# FlashAdapter.net
KiCad netlist of a schematic drawn in EAGLE
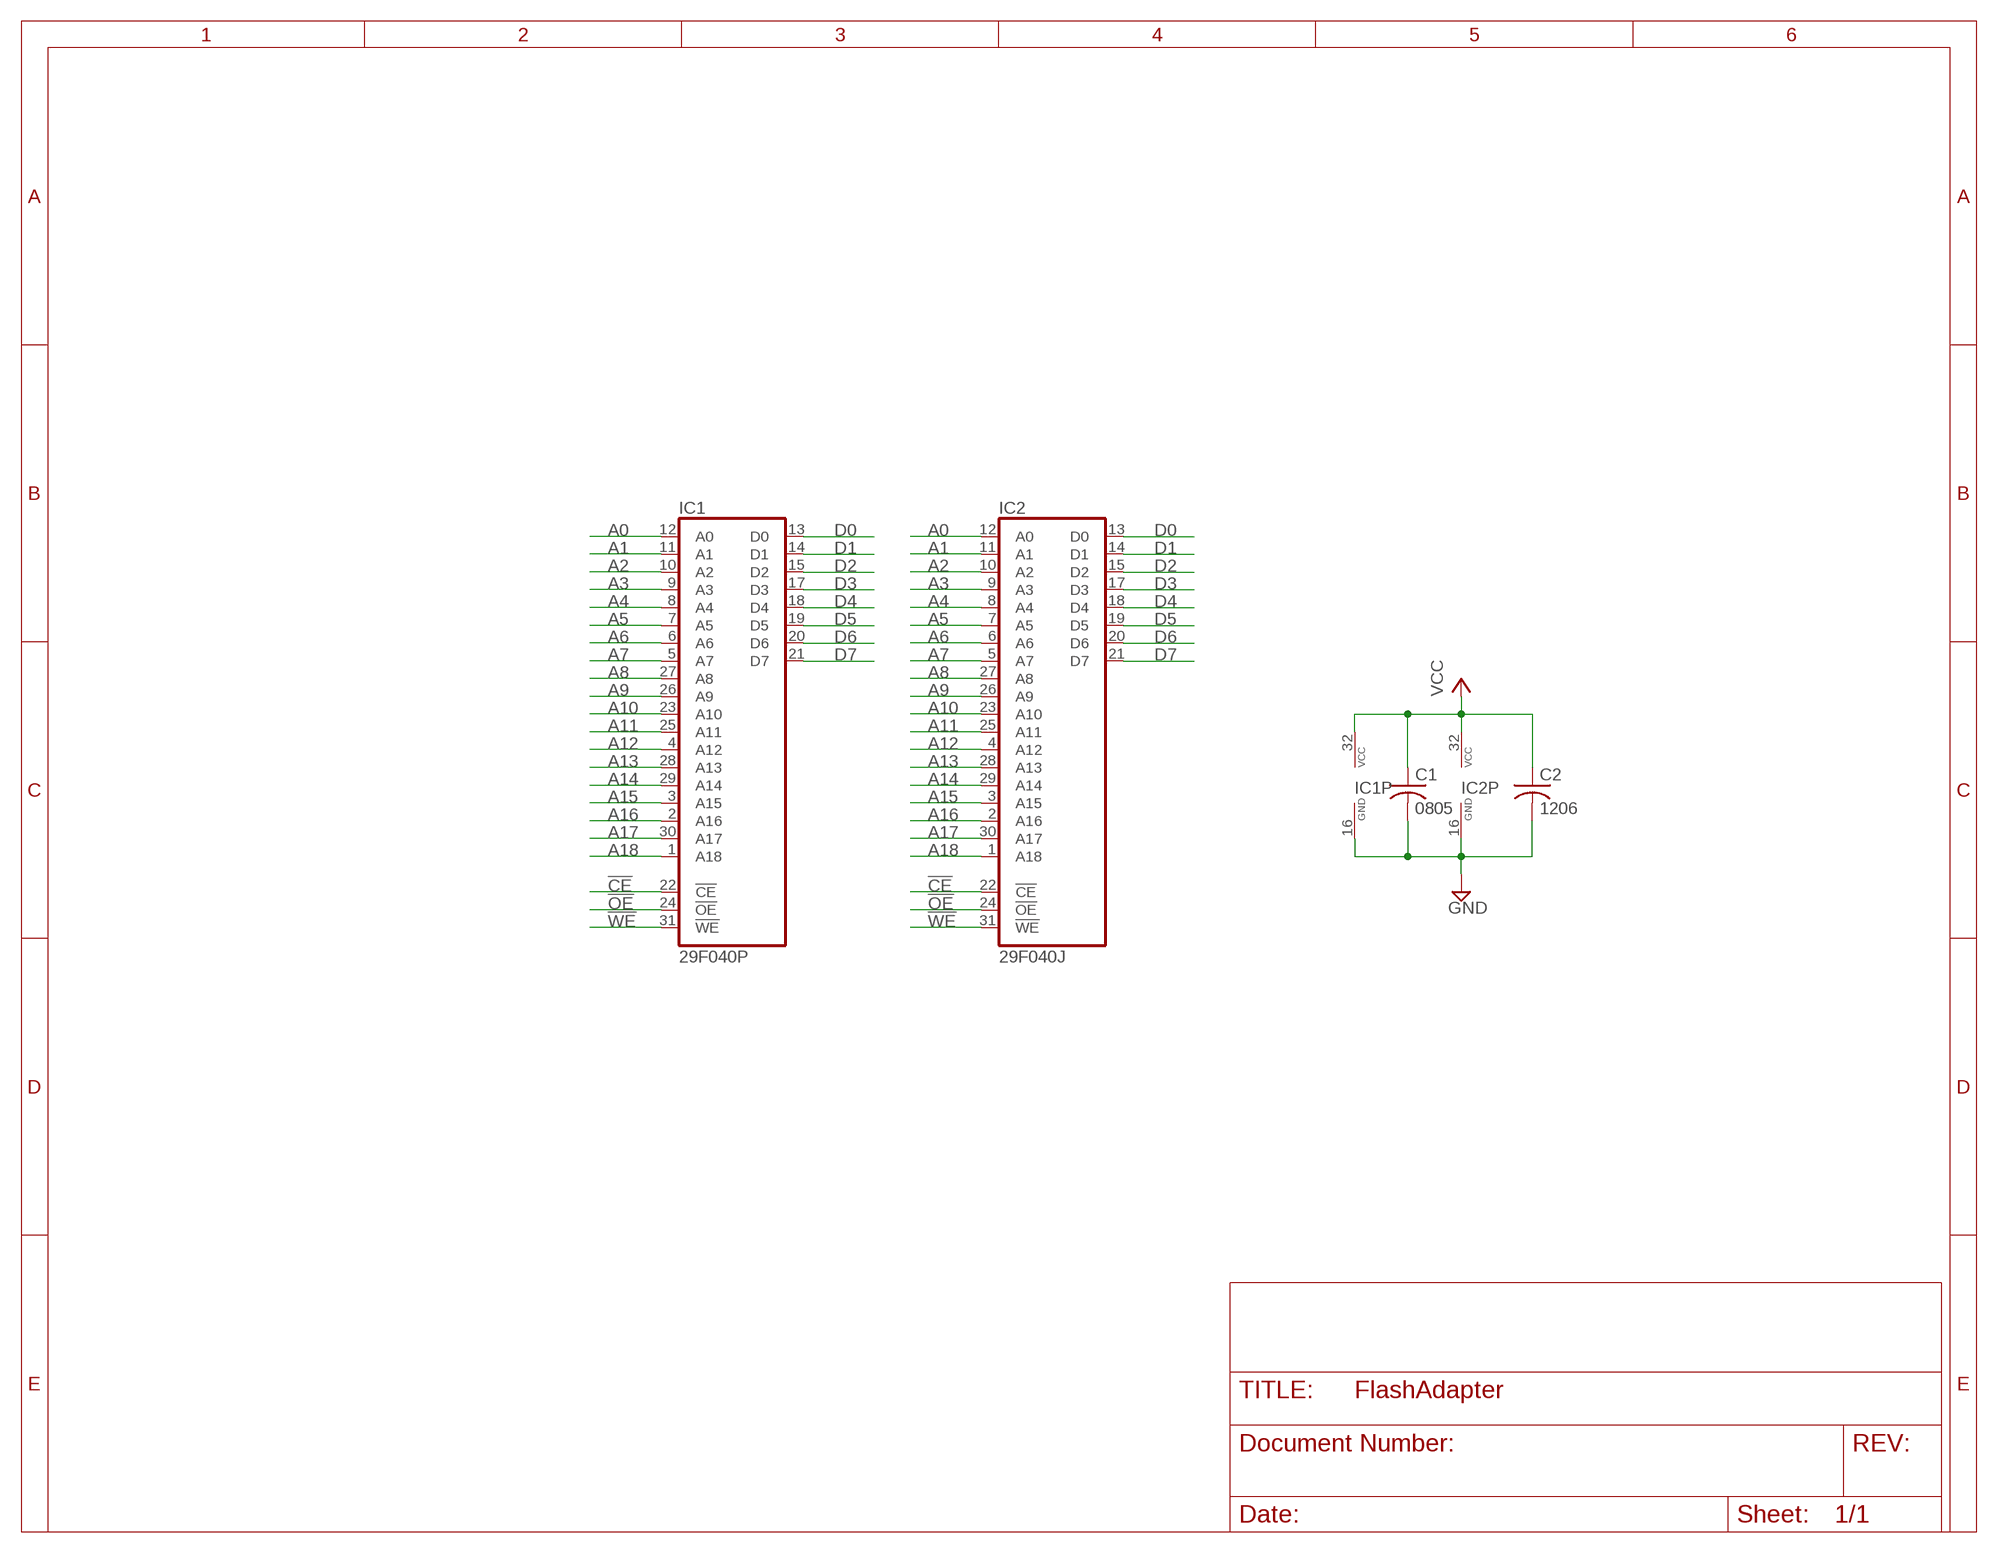
[diagram p0: schematic, sheet 1]

(export (version "E")
  (design (tool "Eeschema 10.0.6"))
  (components
    (comp (ref "C1")
      (value "0805")
      (footprint "eagle-import:C0805")
      (libsource (lib "eagle-import") (part "C-USC0805"))
    )
    (comp (ref "C2")
      (value "1206")
      (footprint "eagle-import:C1206")
      (libsource (lib "eagle-import") (part "C-USC1206"))
    )
    (comp (ref "IC1")
      (value "29F040P")
      (footprint "eagle-import:DIL32-3")
      (libsource (lib "eagle-import") (part "29F040P"))
    )
    (comp (ref "IC2")
      (value "29F040J")
      (footprint "eagle-import:S32")
      (libsource (lib "eagle-import") (part "29F040J"))
    )
  )
  (nets
    (net (code "1") (name "/A0") (class "Default")
      (node (ref "IC1") (pin "12") (pinfunction "A0_12") (pintype "input"))
      (node (ref "IC2") (pin "12") (pinfunction "A0_12") (pintype "input"))
    )
    (net (code "2") (name "/A1") (class "Default")
      (node (ref "IC1") (pin "11") (pinfunction "A1_11") (pintype "input"))
      (node (ref "IC2") (pin "11") (pinfunction "A1_11") (pintype "input"))
    )
    (net (code "3") (name "/A2") (class "Default")
      (node (ref "IC1") (pin "10") (pinfunction "A2_10") (pintype "input"))
      (node (ref "IC2") (pin "10") (pinfunction "A2_10") (pintype "input"))
    )
    (net (code "4") (name "/A3") (class "Default")
      (node (ref "IC1") (pin "9") (pinfunction "A3_9") (pintype "input"))
      (node (ref "IC2") (pin "9") (pinfunction "A3_9") (pintype "input"))
    )
    (net (code "5") (name "/A4") (class "Default")
      (node (ref "IC1") (pin "8") (pinfunction "A4_8") (pintype "input"))
      (node (ref "IC2") (pin "8") (pinfunction "A4_8") (pintype "input"))
    )
    (net (code "6") (name "/A5") (class "Default")
      (node (ref "IC1") (pin "7") (pinfunction "A5_7") (pintype "input"))
      (node (ref "IC2") (pin "7") (pinfunction "A5_7") (pintype "input"))
    )
    (net (code "7") (name "/A6") (class "Default")
      (node (ref "IC1") (pin "6") (pinfunction "A6_6") (pintype "input"))
      (node (ref "IC2") (pin "6") (pinfunction "A6_6") (pintype "input"))
    )
    (net (code "8") (name "/A7") (class "Default")
      (node (ref "IC1") (pin "5") (pinfunction "A7_5") (pintype "input"))
      (node (ref "IC2") (pin "5") (pinfunction "A7_5") (pintype "input"))
    )
    (net (code "9") (name "/A8") (class "Default")
      (node (ref "IC1") (pin "27") (pinfunction "A8_27") (pintype "input"))
      (node (ref "IC2") (pin "27") (pinfunction "A8_27") (pintype "input"))
    )
    (net (code "10") (name "/A9") (class "Default")
      (node (ref "IC1") (pin "26") (pinfunction "A9_26") (pintype "input"))
      (node (ref "IC2") (pin "26") (pinfunction "A9_26") (pintype "input"))
    )
    (net (code "11") (name "/A10") (class "Default")
      (node (ref "IC1") (pin "23") (pinfunction "A10_23") (pintype "input"))
      (node (ref "IC2") (pin "23") (pinfunction "A10_23") (pintype "input"))
    )
    (net (code "12") (name "/A11") (class "Default")
      (node (ref "IC1") (pin "25") (pinfunction "A11_25") (pintype "input"))
      (node (ref "IC2") (pin "25") (pinfunction "A11_25") (pintype "input"))
    )
    (net (code "13") (name "/A12") (class "Default")
      (node (ref "IC1") (pin "4") (pinfunction "A12_4") (pintype "input"))
      (node (ref "IC2") (pin "4") (pinfunction "A12_4") (pintype "input"))
    )
    (net (code "14") (name "/A13") (class "Default")
      (node (ref "IC1") (pin "28") (pinfunction "A13_28") (pintype "input"))
      (node (ref "IC2") (pin "28") (pinfunction "A13_28") (pintype "input"))
    )
    (net (code "15") (name "/A14") (class "Default")
      (node (ref "IC1") (pin "29") (pinfunction "A14_29") (pintype "input"))
      (node (ref "IC2") (pin "29") (pinfunction "A14_29") (pintype "input"))
    )
    (net (code "16") (name "/A15") (class "Default")
      (node (ref "IC1") (pin "3") (pinfunction "A15_3") (pintype "input"))
      (node (ref "IC2") (pin "3") (pinfunction "A15_3") (pintype "input"))
    )
    (net (code "17") (name "/A16") (class "Default")
      (node (ref "IC1") (pin "2") (pinfunction "A16_2") (pintype "input"))
      (node (ref "IC2") (pin "2") (pinfunction "A16_2") (pintype "input"))
    )
    (net (code "18") (name "/A17") (class "Default")
      (node (ref "IC1") (pin "30") (pinfunction "A17_30") (pintype "input"))
      (node (ref "IC2") (pin "30") (pinfunction "A17_30") (pintype "input"))
    )
    (net (code "19") (name "/A18") (class "Default")
      (node (ref "IC1") (pin "1") (pinfunction "A18_1") (pintype "input"))
      (node (ref "IC2") (pin "1") (pinfunction "A18_1") (pintype "input"))
    )
    (net (code "20") (name "/D0") (class "Default")
      (node (ref "IC1") (pin "13") (pinfunction "D0_13") (pintype "tri_state"))
      (node (ref "IC2") (pin "13") (pinfunction "D0_13") (pintype "tri_state"))
    )
    (net (code "21") (name "/D1") (class "Default")
      (node (ref "IC1") (pin "14") (pinfunction "D1_14") (pintype "tri_state"))
      (node (ref "IC2") (pin "14") (pinfunction "D1_14") (pintype "tri_state"))
    )
    (net (code "22") (name "/D2") (class "Default")
      (node (ref "IC1") (pin "15") (pinfunction "D2_15") (pintype "tri_state"))
      (node (ref "IC2") (pin "15") (pinfunction "D2_15") (pintype "tri_state"))
    )
    (net (code "23") (name "/D3") (class "Default")
      (node (ref "IC1") (pin "17") (pinfunction "D3_17") (pintype "tri_state"))
      (node (ref "IC2") (pin "17") (pinfunction "D3_17") (pintype "tri_state"))
    )
    (net (code "24") (name "/D4") (class "Default")
      (node (ref "IC1") (pin "18") (pinfunction "D4_18") (pintype "tri_state"))
      (node (ref "IC2") (pin "18") (pinfunction "D4_18") (pintype "tri_state"))
    )
    (net (code "25") (name "/D5") (class "Default")
      (node (ref "IC1") (pin "19") (pinfunction "D5_19") (pintype "tri_state"))
      (node (ref "IC2") (pin "19") (pinfunction "D5_19") (pintype "tri_state"))
    )
    (net (code "26") (name "/D6") (class "Default")
      (node (ref "IC1") (pin "20") (pinfunction "D6_20") (pintype "tri_state"))
      (node (ref "IC2") (pin "20") (pinfunction "D6_20") (pintype "tri_state"))
    )
    (net (code "27") (name "/D7") (class "Default")
      (node (ref "IC1") (pin "21") (pinfunction "D7_21") (pintype "tri_state"))
      (node (ref "IC2") (pin "21") (pinfunction "D7_21") (pintype "tri_state"))
    )
    (net (code "28") (name "/~{CE}") (class "Default")
      (node (ref "IC1") (pin "22") (pinfunction "~{CE}_22") (pintype "input"))
      (node (ref "IC2") (pin "22") (pinfunction "~{CE}_22") (pintype "input"))
    )
    (net (code "29") (name "/~{OE}") (class "Default")
      (node (ref "IC1") (pin "24") (pinfunction "~{OE}_24") (pintype "input"))
      (node (ref "IC2") (pin "24") (pinfunction "~{OE}_24") (pintype "input"))
    )
    (net (code "30") (name "/~{WE}") (class "Default")
      (node (ref "IC1") (pin "31") (pinfunction "~{WE}_31") (pintype "input"))
      (node (ref "IC2") (pin "31") (pinfunction "~{WE}_31") (pintype "input"))
    )
    (net (code "31") (name "GND") (class "Default")
      (node (ref "C1") (pin "2") (pinfunction "2_2") (pintype "passive"))
      (node (ref "C2") (pin "2") (pinfunction "2_2") (pintype "passive"))
      (node (ref "IC1") (pin "16") (pinfunction "GND_16") (pintype "power_in"))
      (node (ref "IC2") (pin "16") (pinfunction "GND_16") (pintype "power_in"))
    )
    (net (code "32") (name "VCC") (class "Default")
      (node (ref "C1") (pin "1") (pinfunction "1_1") (pintype "passive"))
      (node (ref "C2") (pin "1") (pinfunction "1_1") (pintype "passive"))
      (node (ref "IC1") (pin "32") (pinfunction "VCC_32") (pintype "power_in"))
      (node (ref "IC2") (pin "32") (pinfunction "VCC_32") (pintype "power_in"))
    )
  )
)
